# MTRduino_Rev2_2.net
KiCad netlist of a schematic drawn in EAGLE
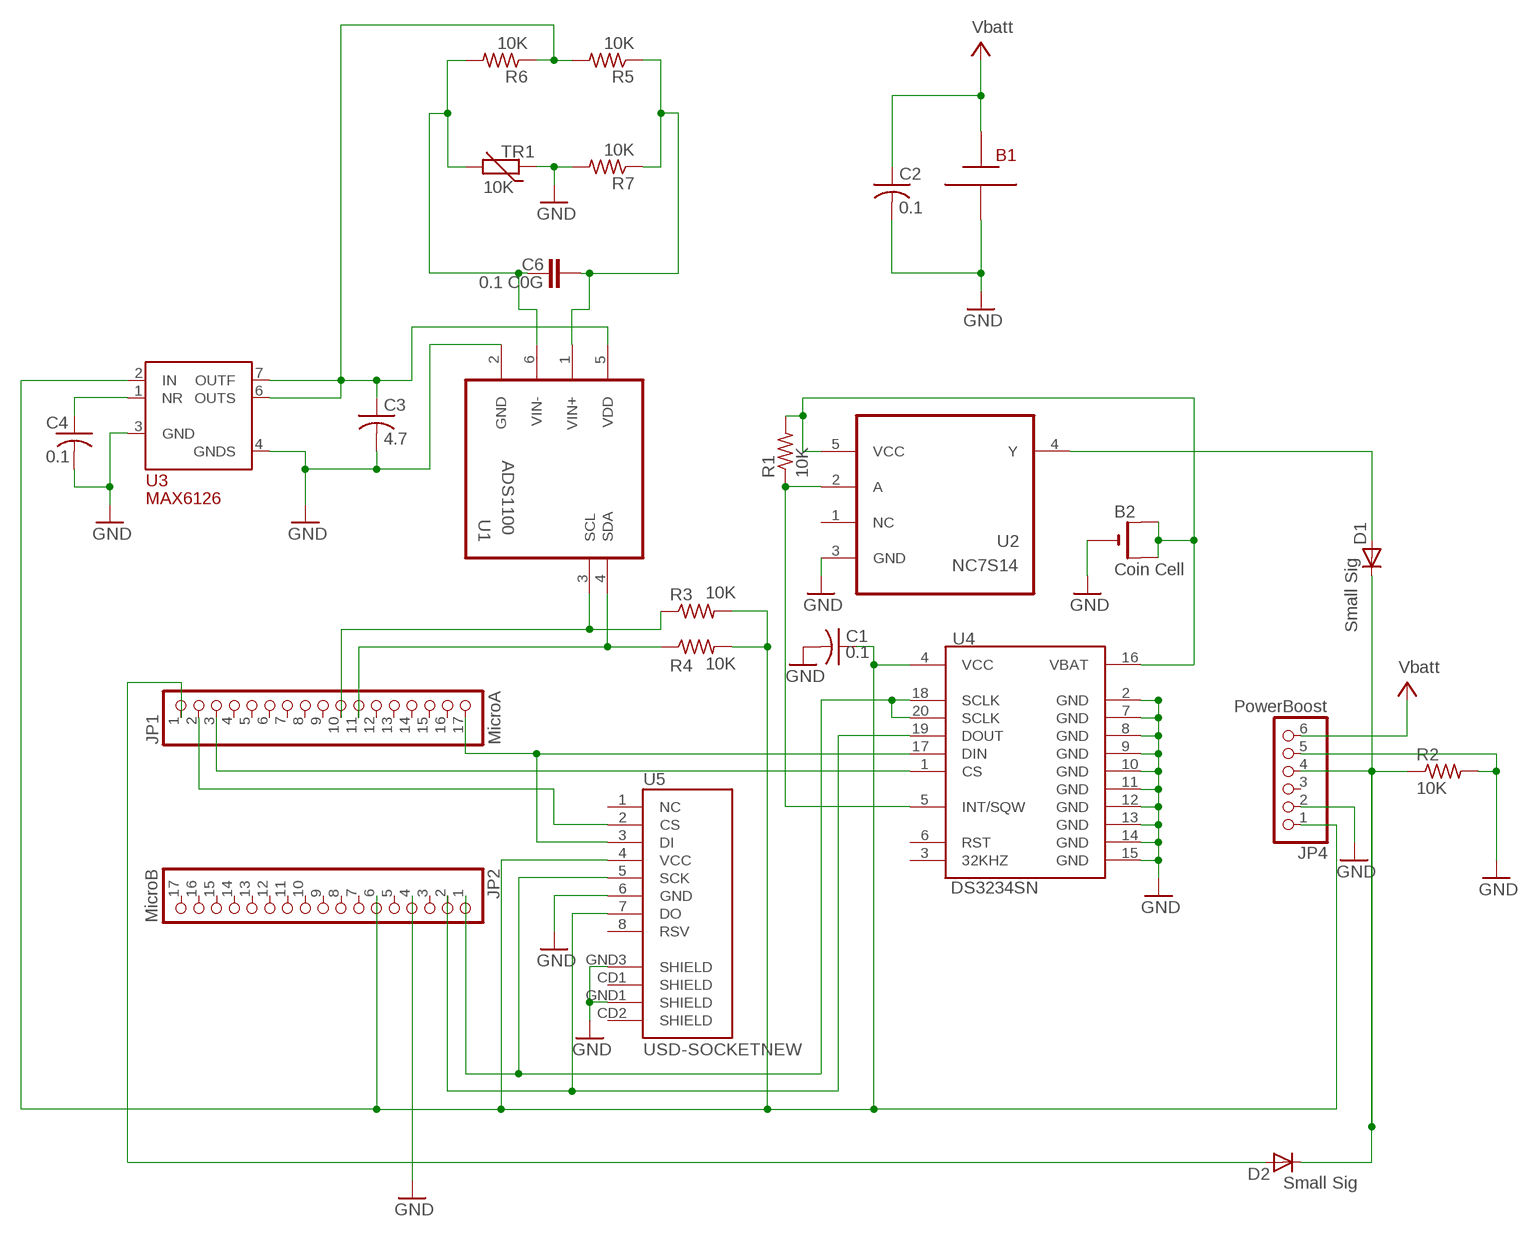
[diagram p0: schematic, sheet 1]

(export (version "E")
  (design (tool "Eeschema 10.0.6"))
  (components
    (comp (ref "B1")
      (value "2x AA BATT")
      (footprint "eagle-import:BATT_AA2")
      (libsource (lib "eagle-import") (part "BATT_AA2"))
    )
    (comp (ref "B2")
      (value "Coin Cell")
      (footprint "eagle-import:CR1220-SMD")
      (libsource (lib "eagle-import") (part "CR1220SMT"))
    )
    (comp (ref "C1")
      (value "0.1")
      (footprint "eagle-import:C0603")
      (libsource (lib "eagle-import") (part "C-USC0603"))
    )
    (comp (ref "C2")
      (value "0.1")
      (footprint "eagle-import:C0603")
      (libsource (lib "eagle-import") (part "C-USC0603"))
    )
    (comp (ref "C3")
      (value "4.7")
      (footprint "eagle-import:C0603")
      (libsource (lib "eagle-import") (part "C-USC0603"))
    )
    (comp (ref "C4")
      (value "0.1")
      (footprint "eagle-import:C0603")
      (libsource (lib "eagle-import") (part "C-USC0603"))
    )
    (comp (ref "C6")
      (value "0.1 C0G")
      (footprint "eagle-import:C0603")
      (libsource (lib "eagle-import") (part "C-EUC0603"))
    )
    (comp (ref "D1")
      (value "Small Sig")
      (footprint "eagle-import:SOD-323F")
      (libsource (lib "eagle-import") (part "DIODESOD-323F"))
    )
    (comp (ref "D2")
      (value "Small Sig")
      (footprint "eagle-import:SOD-323F")
      (libsource (lib "eagle-import") (part "DIODESOD-323F"))
    )
    (comp (ref "JP1")
      (value "MicroA")
      (footprint "eagle-import:1X17")
      (libsource (lib "eagle-import") (part "PINHD-1X17"))
    )
    (comp (ref "JP2")
      (value "MicroB")
      (footprint "eagle-import:1X17")
      (libsource (lib "eagle-import") (part "PINHD-1X17"))
    )
    (comp (ref "JP4")
      (value "PowerBoost")
      (footprint "eagle-import:1X06")
      (libsource (lib "eagle-import") (part "PINHD-1X6"))
    )
    (comp (ref "R1")
      (value "10K")
      (footprint "eagle-import:R0603")
      (libsource (lib "eagle-import") (part "R-US_R0603"))
    )
    (comp (ref "R2")
      (value "10K")
      (footprint "eagle-import:R0603")
      (libsource (lib "eagle-import") (part "R-US_R0603"))
    )
    (comp (ref "R3")
      (value "10K")
      (footprint "eagle-import:R0603")
      (libsource (lib "eagle-import") (part "R-US_R0603"))
    )
    (comp (ref "R4")
      (value "10K")
      (footprint "eagle-import:R0603")
      (libsource (lib "eagle-import") (part "R-US_R0603"))
    )
    (comp (ref "R5")
      (value "10K")
      (footprint "eagle-import:R0603")
      (libsource (lib "eagle-import") (part "R-US_R0603"))
    )
    (comp (ref "R6")
      (value "10K")
      (footprint "eagle-import:R0603")
      (libsource (lib "eagle-import") (part "R-US_R0603"))
    )
    (comp (ref "R7")
      (value "10K")
      (footprint "eagle-import:R0603")
      (libsource (lib "eagle-import") (part "R-US_R0603"))
    )
    (comp (ref "TR1")
      (value "10K")
      (footprint "eagle-import:R-5")
      (libsource (lib "eagle-import") (part "THERMISTOR_R-5"))
    )
    (comp (ref "U1")
      (value "ADS1100")
      (footprint "eagle-import:SOT95P280X145-6N")
      (fields (field (name "MPN") "ADS1100A0IDBVT"))
      (libsource (lib "eagle-import") (part "ADS1100A0IDBVT"))
    )
    (comp (ref "U2")
      (value "NC7S14")
      (footprint "eagle-import:SOT95P280X145-5N")
      (fields (field (name "MPN") "1P1G14MDBVREPG4"))
      (libsource (lib "eagle-import") (part "1P1G14MDBVREPG4"))
    )
    (comp (ref "U3")
      (value "MAX6126")
      (footprint "eagle-import:SOIC127P600X175-8N")
      (libsource (lib "eagle-import") (part "MAX6126"))
    )
    (comp (ref "U4")
      (value "DS3234SN")
      (footprint "eagle-import:DS3234")
      (libsource (lib "eagle-import") (part "DS3234"))
    )
    (comp (ref "U5")
      (value "USD-SOCKETNEW")
      (footprint "eagle-import:MICRO-SD-SOCKET-PP")
      (libsource (lib "eagle-import") (part "USD-SOCKETNEW"))
    )
  )
  (nets
    (net (code "1") (name "GND") (class "Default")
      (node (ref "B1") (pin "-") (pinfunction "-_-") (pintype "bidirectional"))
      (node (ref "B2") (pin "-") (pinfunction "-_-") (pintype "passive"))
      (node (ref "C1") (pin "2") (pinfunction "2_2") (pintype "passive"))
      (node (ref "C2") (pin "2") (pinfunction "2_2") (pintype "passive"))
      (node (ref "C3") (pin "2") (pinfunction "2_2") (pintype "passive"))
      (node (ref "C4") (pin "2") (pinfunction "2_2") (pintype "passive"))
      (node (ref "JP2") (pin "4") (pinfunction "4_4") (pintype "passive"))
      (node (ref "JP4") (pin "2") (pinfunction "2_2") (pintype "passive"))
      (node (ref "JP4") (pin "5") (pinfunction "5_5") (pintype "passive"))
      (node (ref "R2") (pin "2") (pinfunction "2_2") (pintype "passive"))
      (node (ref "R7") (pin "2") (pinfunction "2_2") (pintype "passive"))
      (node (ref "TR1") (pin "1") (pinfunction "1_1") (pintype "passive"))
      (node (ref "U1") (pin "2") (pinfunction "GND_2") (pintype "passive"))
      (node (ref "U2") (pin "3") (pinfunction "GND_3") (pintype "passive"))
      (node (ref "U3") (pin "3") (pinfunction "GND_3") (pintype "input"))
      (node (ref "U3") (pin "4") (pinfunction "GNDS_4") (pintype "input"))
      (node (ref "U4") (pin "10") (pinfunction "GND_10") (pintype "bidirectional"))
      (node (ref "U4") (pin "11") (pinfunction "GND_11") (pintype "bidirectional"))
      (node (ref "U4") (pin "12") (pinfunction "GND_12") (pintype "bidirectional"))
      (node (ref "U4") (pin "13") (pinfunction "GND_13") (pintype "bidirectional"))
      (node (ref "U4") (pin "14") (pinfunction "GND_14") (pintype "bidirectional"))
      (node (ref "U4") (pin "15") (pinfunction "GND_15") (pintype "bidirectional"))
      (node (ref "U4") (pin "2") (pinfunction "GND_2") (pintype "bidirectional"))
      (node (ref "U4") (pin "7") (pinfunction "GND_7") (pintype "bidirectional"))
      (node (ref "U4") (pin "8") (pinfunction "GND_8") (pintype "bidirectional"))
      (node (ref "U4") (pin "9") (pinfunction "GND_9") (pintype "bidirectional"))
      (node (ref "U5") (pin "6") (pinfunction "GND_6") (pintype "bidirectional"))
      (node (ref "U5") (pin "GND1") (pinfunction "SHIELD_GND1") (pintype "bidirectional"))
      (node (ref "U5") (pin "GND3") (pinfunction "SHIELD_GND3") (pintype "bidirectional"))
    )
    (net (code "2") (name "Net-(B2-+)") (class "Default")
      (node (ref "B2") (pin "+$1") (pinfunction "+_+$1") (pintype "passive"))
      (node (ref "B2") (pin "+$2") (pinfunction "+1_+$2") (pintype "passive"))
      (node (ref "R1") (pin "2") (pinfunction "2_2") (pintype "passive"))
      (node (ref "U2") (pin "5") (pinfunction "VCC_5") (pintype "power_in"))
      (node (ref "U4") (pin "16") (pinfunction "VBAT_16") (pintype "bidirectional"))
    )
    (net (code "3") (name "Net-(D1-PadC)") (class "Default")
      (node (ref "D1") (pin "C") (pinfunction "C_C") (pintype "passive"))
      (node (ref "D2") (pin "C") (pinfunction "C_C") (pintype "passive"))
      (node (ref "JP4") (pin "4") (pinfunction "4_4") (pintype "passive"))
      (node (ref "R2") (pin "1") (pinfunction "1_1") (pintype "passive"))
    )
    (net (code "4") (name "Net-(D2-PadA)") (class "Default")
      (node (ref "D2") (pin "A") (pinfunction "A_A") (pintype "passive"))
      (node (ref "JP1") (pin "1") (pinfunction "1_1") (pintype "passive"))
    )
    (net (code "5") (name "Net-(U1-SCL)") (class "Default")
      (node (ref "JP1") (pin "10") (pinfunction "10_10") (pintype "passive"))
      (node (ref "R3") (pin "1") (pinfunction "1_1") (pintype "passive"))
      (node (ref "U1") (pin "3") (pinfunction "SCL_3") (pintype "output"))
    )
    (net (code "6") (name "Net-(U1-SDA)") (class "Default")
      (node (ref "JP1") (pin "11") (pinfunction "11_11") (pintype "passive"))
      (node (ref "R4") (pin "1") (pinfunction "1_1") (pintype "passive"))
      (node (ref "U1") (pin "4") (pinfunction "SDA_4") (pintype "output"))
    )
    (net (code "7") (name "Net-(U1-VDD)") (class "Default")
      (node (ref "C3") (pin "1") (pinfunction "1_1") (pintype "passive"))
      (node (ref "R5") (pin "2") (pinfunction "2_2") (pintype "passive"))
      (node (ref "R6") (pin "1") (pinfunction "1_1") (pintype "passive"))
      (node (ref "U1") (pin "5") (pinfunction "VDD_5") (pintype "power_in"))
      (node (ref "U3") (pin "6") (pinfunction "OUTS_6") (pintype "output"))
      (node (ref "U3") (pin "7") (pinfunction "OUTF_7") (pintype "output"))
    )
    (net (code "8") (name "Net-(U1-VIN+)") (class "Default")
      (node (ref "C6") (pin "2") (pinfunction "2_2") (pintype "passive"))
      (node (ref "R5") (pin "1") (pinfunction "1_1") (pintype "passive"))
      (node (ref "R7") (pin "1") (pinfunction "1_1") (pintype "passive"))
      (node (ref "U1") (pin "1") (pinfunction "VIN+_1") (pintype "input"))
    )
    (net (code "9") (name "Net-(U1-VIN-)") (class "Default")
      (node (ref "C6") (pin "1") (pinfunction "1_1") (pintype "passive"))
      (node (ref "R6") (pin "2") (pinfunction "2_2") (pintype "passive"))
      (node (ref "TR1") (pin "2") (pinfunction "2_2") (pintype "passive"))
      (node (ref "U1") (pin "6") (pinfunction "VIN-_6") (pintype "input"))
    )
    (net (code "10") (name "Net-(U2-A)") (class "Default")
      (node (ref "R1") (pin "1") (pinfunction "1_1") (pintype "passive"))
      (node (ref "U2") (pin "2") (pinfunction "A_2") (pintype "input"))
      (node (ref "U4") (pin "5") (pinfunction "INT/SQW_5") (pintype "bidirectional"))
    )
    (net (code "11") (name "Net-(U2-Y)") (class "Default")
      (node (ref "D1") (pin "A") (pinfunction "A_A") (pintype "passive"))
      (node (ref "U2") (pin "4") (pinfunction "Y_4") (pintype "output"))
    )
    (net (code "12") (name "Net-(U3-IN)") (class "Default")
      (node (ref "C1") (pin "1") (pinfunction "1_1") (pintype "passive"))
      (node (ref "JP2") (pin "6") (pinfunction "6_6") (pintype "passive"))
      (node (ref "JP4") (pin "1") (pinfunction "1_1") (pintype "passive"))
      (node (ref "R3") (pin "2") (pinfunction "2_2") (pintype "passive"))
      (node (ref "R4") (pin "2") (pinfunction "2_2") (pintype "passive"))
      (node (ref "U3") (pin "2") (pinfunction "IN_2") (pintype "input"))
      (node (ref "U4") (pin "4") (pinfunction "VCC_4") (pintype "bidirectional"))
      (node (ref "U5") (pin "4") (pinfunction "VCC_4") (pintype "bidirectional"))
    )
    (net (code "13") (name "Net-(U3-NR)") (class "Default")
      (node (ref "C4") (pin "1") (pinfunction "1_1") (pintype "passive"))
      (node (ref "U3") (pin "1") (pinfunction "NR_1") (pintype "bidirectional"))
    )
    (net (code "14") (name "Net-(U4-CS)") (class "Default")
      (node (ref "JP1") (pin "3") (pinfunction "3_3") (pintype "passive"))
      (node (ref "U4") (pin "1") (pinfunction "CS_1") (pintype "bidirectional"))
    )
    (net (code "15") (name "Net-(U4-DIN)") (class "Default")
      (node (ref "JP1") (pin "17") (pinfunction "17_17") (pintype "passive"))
      (node (ref "U4") (pin "17") (pinfunction "DIN_17") (pintype "bidirectional"))
      (node (ref "U5") (pin "3") (pinfunction "DI_3") (pintype "bidirectional"))
    )
    (net (code "16") (name "Net-(U4-DOUT)") (class "Default")
      (node (ref "JP2") (pin "2") (pinfunction "2_2") (pintype "passive"))
      (node (ref "U4") (pin "19") (pinfunction "DOUT_19") (pintype "bidirectional"))
      (node (ref "U5") (pin "7") (pinfunction "DO_7") (pintype "bidirectional"))
    )
    (net (code "17") (name "Net-(U5-CS)") (class "Default")
      (node (ref "JP1") (pin "2") (pinfunction "2_2") (pintype "passive"))
      (node (ref "U5") (pin "2") (pinfunction "CS_2") (pintype "bidirectional"))
    )
    (net (code "18") (name "Net-(U5-SCK)") (class "Default")
      (node (ref "JP2") (pin "1") (pinfunction "1_1") (pintype "passive"))
      (node (ref "U4") (pin "18") (pinfunction "SCLK_18") (pintype "bidirectional"))
      (node (ref "U4") (pin "20") (pinfunction "SCLK_20") (pintype "bidirectional"))
      (node (ref "U5") (pin "5") (pinfunction "SCK_5") (pintype "bidirectional"))
    )
    (net (code "19") (name "Vbatt") (class "Default")
      (node (ref "B1") (pin "+") (pinfunction "+_+") (pintype "bidirectional"))
      (node (ref "C2") (pin "1") (pinfunction "1_1") (pintype "passive"))
      (node (ref "JP4") (pin "6") (pinfunction "6_6") (pintype "passive"))
    )
    (net (code "20") (name "unconnected-(JP1-Pad4)") (class "Default")
      (node (ref "JP1") (pin "4") (pinfunction "4_4") (pintype "passive"))
    )
    (net (code "21") (name "unconnected-(JP1-Pad5)") (class "Default")
      (node (ref "JP1") (pin "5") (pinfunction "5_5") (pintype "passive"))
    )
    (net (code "22") (name "unconnected-(JP1-Pad6)") (class "Default")
      (node (ref "JP1") (pin "6") (pinfunction "6_6") (pintype "passive"))
    )
    (net (code "23") (name "unconnected-(JP1-Pad7)") (class "Default")
      (node (ref "JP1") (pin "7") (pinfunction "7_7") (pintype "passive"))
    )
    (net (code "24") (name "unconnected-(JP1-Pad8)") (class "Default")
      (node (ref "JP1") (pin "8") (pinfunction "8_8") (pintype "passive"))
    )
    (net (code "25") (name "unconnected-(JP1-Pad9)") (class "Default")
      (node (ref "JP1") (pin "9") (pinfunction "9_9") (pintype "passive"))
    )
    (net (code "26") (name "unconnected-(JP1-Pad12)") (class "Default")
      (node (ref "JP1") (pin "12") (pinfunction "12_12") (pintype "passive"))
    )
    (net (code "27") (name "unconnected-(JP1-Pad13)") (class "Default")
      (node (ref "JP1") (pin "13") (pinfunction "13_13") (pintype "passive"))
    )
    (net (code "28") (name "unconnected-(JP1-Pad14)") (class "Default")
      (node (ref "JP1") (pin "14") (pinfunction "14_14") (pintype "passive"))
    )
    (net (code "29") (name "unconnected-(JP1-Pad15)") (class "Default")
      (node (ref "JP1") (pin "15") (pinfunction "15_15") (pintype "passive"))
    )
    (net (code "30") (name "unconnected-(JP1-Pad16)") (class "Default")
      (node (ref "JP1") (pin "16") (pinfunction "16_16") (pintype "passive"))
    )
    (net (code "31") (name "unconnected-(JP2-Pad3)") (class "Default")
      (node (ref "JP2") (pin "3") (pinfunction "3_3") (pintype "passive"))
    )
    (net (code "32") (name "unconnected-(JP2-Pad5)") (class "Default")
      (node (ref "JP2") (pin "5") (pinfunction "5_5") (pintype "passive"))
    )
    (net (code "33") (name "unconnected-(JP2-Pad7)") (class "Default")
      (node (ref "JP2") (pin "7") (pinfunction "7_7") (pintype "passive"))
    )
    (net (code "34") (name "unconnected-(JP2-Pad8)") (class "Default")
      (node (ref "JP2") (pin "8") (pinfunction "8_8") (pintype "passive"))
    )
    (net (code "35") (name "unconnected-(JP2-Pad9)") (class "Default")
      (node (ref "JP2") (pin "9") (pinfunction "9_9") (pintype "passive"))
    )
    (net (code "36") (name "unconnected-(JP2-Pad10)") (class "Default")
      (node (ref "JP2") (pin "10") (pinfunction "10_10") (pintype "passive"))
    )
    (net (code "37") (name "unconnected-(JP2-Pad11)") (class "Default")
      (node (ref "JP2") (pin "11") (pinfunction "11_11") (pintype "passive"))
    )
    (net (code "38") (name "unconnected-(JP2-Pad12)") (class "Default")
      (node (ref "JP2") (pin "12") (pinfunction "12_12") (pintype "passive"))
    )
    (net (code "39") (name "unconnected-(JP2-Pad13)") (class "Default")
      (node (ref "JP2") (pin "13") (pinfunction "13_13") (pintype "passive"))
    )
    (net (code "40") (name "unconnected-(JP2-Pad14)") (class "Default")
      (node (ref "JP2") (pin "14") (pinfunction "14_14") (pintype "passive"))
    )
    (net (code "41") (name "unconnected-(JP2-Pad15)") (class "Default")
      (node (ref "JP2") (pin "15") (pinfunction "15_15") (pintype "passive"))
    )
    (net (code "42") (name "unconnected-(JP2-Pad16)") (class "Default")
      (node (ref "JP2") (pin "16") (pinfunction "16_16") (pintype "passive"))
    )
    (net (code "43") (name "unconnected-(JP2-Pad17)") (class "Default")
      (node (ref "JP2") (pin "17") (pinfunction "17_17") (pintype "passive"))
    )
    (net (code "44") (name "unconnected-(JP4-Pad3)") (class "Default")
      (node (ref "JP4") (pin "3") (pinfunction "3_3") (pintype "passive"))
    )
    (net (code "45") (name "unconnected-(U2-NC-Pad1)") (class "Default")
      (node (ref "U2") (pin "1") (pinfunction "NC_1") (pintype "no_connect"))
    )
    (net (code "46") (name "unconnected-(U4-32KHZ-Pad3)") (class "Default")
      (node (ref "U4") (pin "3") (pinfunction "32KHZ_3") (pintype "bidirectional"))
    )
    (net (code "47") (name "unconnected-(U4-RST-Pad6)") (class "Default")
      (node (ref "U4") (pin "6") (pinfunction "RST_6") (pintype "bidirectional"))
    )
    (net (code "48") (name "unconnected-(U5-NC-Pad1)") (class "Default")
      (node (ref "U5") (pin "1") (pinfunction "NC_1") (pintype "bidirectional"))
    )
    (net (code "49") (name "unconnected-(U5-RSV-Pad8)") (class "Default")
      (node (ref "U5") (pin "8") (pinfunction "RSV_8") (pintype "bidirectional"))
    )
    (net (code "50") (name "unconnected-(U5-SHIELD-PadCD1)") (class "Default")
      (node (ref "U5") (pin "CD1") (pinfunction "SHIELD_CD1") (pintype "bidirectional"))
    )
    (net (code "51") (name "unconnected-(U5-SHIELD-PadCD2)") (class "Default")
      (node (ref "U5") (pin "CD2") (pinfunction "SHIELD_CD2") (pintype "bidirectional"))
    )
  )
)
